# TelemetryModule.net
KiCad netlist of a schematic drawn in EAGLE
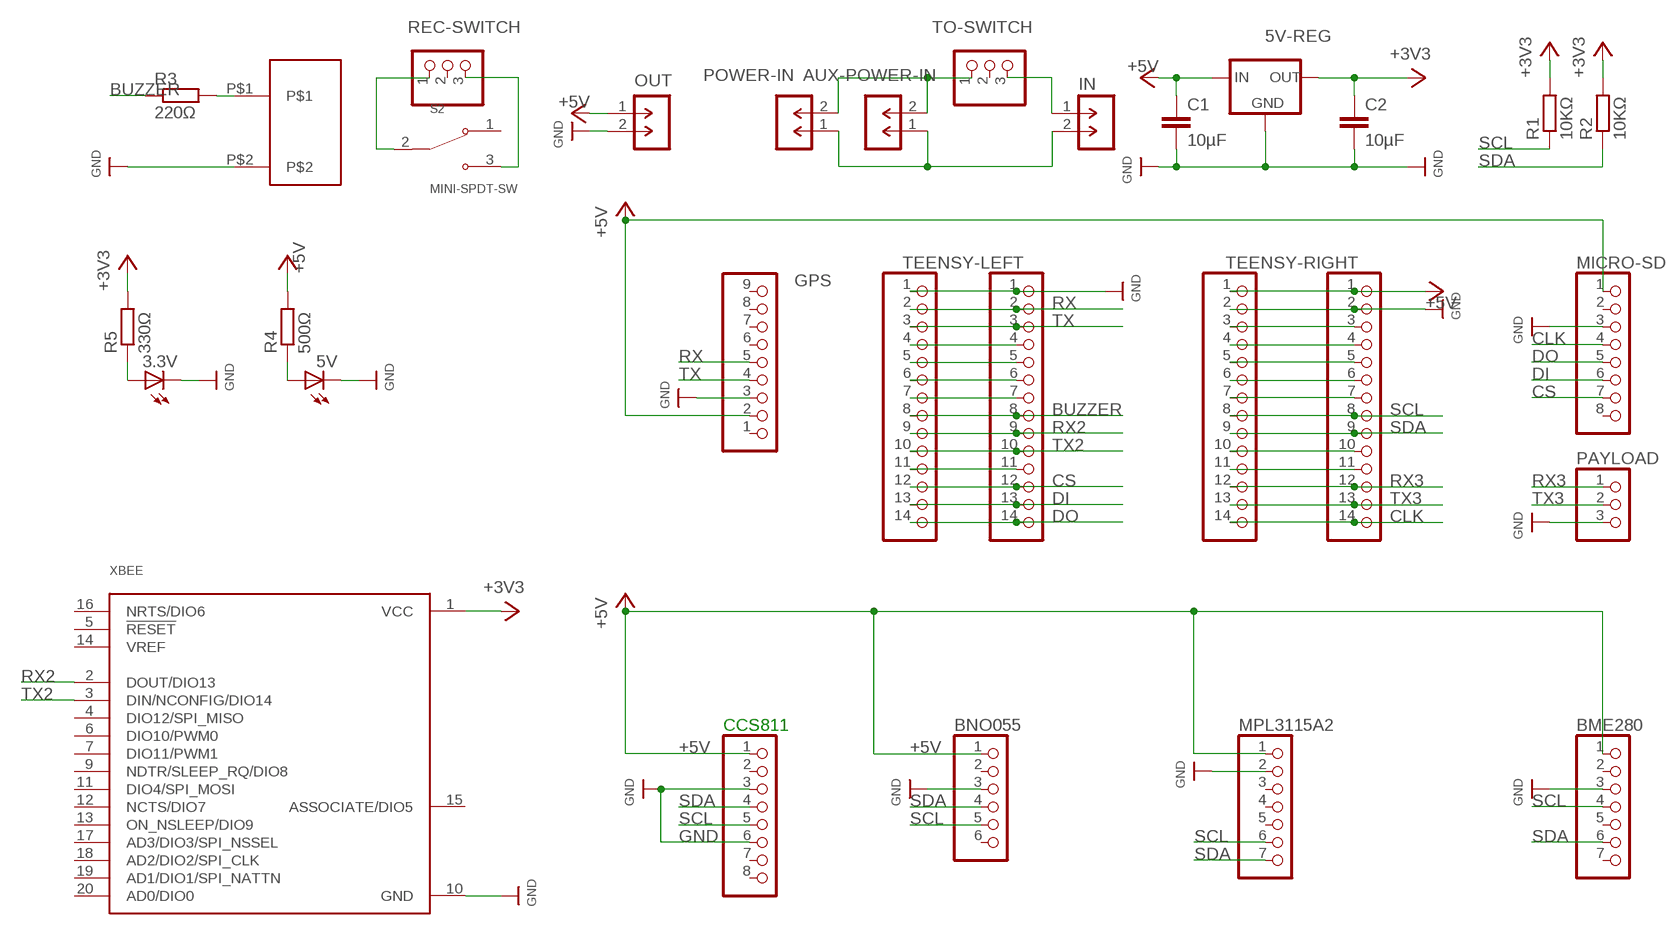
[diagram p0: schematic, sheet 1]

(export (version "E")
  (design (tool "Eeschema 10.0.6"))
  (components
    (comp (ref "3.3V")
      (value "LED5MM")
      (footprint "eagle-import:LED5MM")
      (libsource (lib "eagle-import") (part "LED5MM"))
    )
    (comp (ref "5V")
      (value "LED5MM")
      (footprint "eagle-import:LED5MM")
      (libsource (lib "eagle-import") (part "LED5MM"))
    )
    (comp (ref "5V-REG")
      (value "LD1117V33")
      (footprint "eagle-import:LD1117V33")
      (libsource (lib "eagle-import") (part "LD1117V33"))
    )
    (comp (ref "AUX-POWER-IN")
      (value "M-1X02-SIP-100-40Y")
      (footprint "eagle-import:SIP-100-02-40Y")
      (libsource (lib "eagle-import") (part "M-1X02-SIP-100-40Y"))
    )
    (comp (ref "BME280")
      (value "HEADER-1X770MIL")
      (footprint "eagle-import:1X07_ROUND_70")
      (libsource (lib "eagle-import") (part "HEADER-1X770MIL"))
    )
    (comp (ref "BNO055")
      (value "HEADER-1X676MIL")
      (footprint "eagle-import:1X06_ROUND_76")
      (libsource (lib "eagle-import") (part "HEADER-1X676MIL"))
    )
    (comp (ref "C1")
      (value "10µF")
      (footprint "eagle-import:C2.5-3")
      (libsource (lib "eagle-import") (part "C2,5-3"))
    )
    (comp (ref "C2")
      (value "10µF")
      (footprint "eagle-import:C2.5-3")
      (libsource (lib "eagle-import") (part "C2,5-3"))
    )
    (comp (ref "CCS811")
      (value "HEADER-1X870MIL")
      (footprint "eagle-import:1X08_ROUND_70")
      (libsource (lib "eagle-import") (part "HEADER-1X870MIL"))
    )
    (comp (ref "GPS")
      (value "HEADER-1X970MIL")
      (footprint "eagle-import:1X09_ROUND_70")
      (libsource (lib "eagle-import") (part "HEADER-1X970MIL"))
    )
    (comp (ref "IN")
      (value "M-1X02-SIP-100-40Y")
      (footprint "eagle-import:SIP-100-02-40Y")
      (libsource (lib "eagle-import") (part "M-1X02-SIP-100-40Y"))
    )
    (comp (ref "MICRO-SD")
      (value "PINHD-1X8BIG")
      (footprint "eagle-import:1X08-BIG")
      (libsource (lib "eagle-import") (part "PINHD-1X8BIG"))
    )
    (comp (ref "MPL3115A2")
      (value "HEADER-1X770MIL")
      (footprint "eagle-import:1X07_ROUND_70")
      (libsource (lib "eagle-import") (part "HEADER-1X770MIL"))
    )
    (comp (ref "OUT")
      (value "M-1X02-SIP-100-40Y")
      (footprint "eagle-import:SIP-100-02-40Y")
      (libsource (lib "eagle-import") (part "M-1X02-SIP-100-40Y"))
    )
    (comp (ref "PAYLOAD")
      (value "PINHD-1X3CB")
      (footprint "eagle-import:1X03-CLEANBIG")
      (libsource (lib "eagle-import") (part "PINHD-1X3CB"))
    )
    (comp (ref "POWER-IN")
      (value "M-1X02-SIP-100-40Y")
      (footprint "eagle-import:SIP-100-02-40Y")
      (libsource (lib "eagle-import") (part "M-1X02-SIP-100-40Y"))
    )
    (comp (ref "R1")
      (value "10KΩ")
      (footprint "eagle-import:0207_10")
      (libsource (lib "eagle-import") (part "R-EU_0207/10"))
    )
    (comp (ref "R2")
      (value "10KΩ")
      (footprint "eagle-import:0207_10")
      (libsource (lib "eagle-import") (part "R-EU_0207/10"))
    )
    (comp (ref "R3")
      (value "220Ω")
      (footprint "eagle-import:0207_10")
      (libsource (lib "eagle-import") (part "R-EU_0207/10"))
    )
    (comp (ref "R4")
      (value "500Ω")
      (footprint "eagle-import:0207_10")
      (libsource (lib "eagle-import") (part "R-EU_0207/10"))
    )
    (comp (ref "R5")
      (value "330Ω")
      (footprint "eagle-import:0207_10")
      (libsource (lib "eagle-import") (part "R-EU_0207/10"))
    )
    (comp (ref "REC-SWITCH")
      (value "PINHD-1X3CB")
      (footprint "eagle-import:1X03-CLEANBIG")
      (libsource (lib "eagle-import") (part "PINHD-1X3CB"))
    )
    (comp (ref "S2")
      (value "MINI-SPDT-SW")
      (footprint "eagle-import:SW_MINI-SPDT-SW")
      (fields (field (name "MF") "Gravitech"))
      (libsource (lib "eagle-import") (part "MINI-SPDT-SW"))
    )
    (comp (ref "TEENSY-LEFT")
      (value "PINHD-1X14-CB")
      (footprint "eagle-import:1X14-CB")
      (libsource (lib "eagle-import") (part "PINHD-1X14-CB"))
    )
    (comp (ref "TEENSY-LEFT-DUPE")
      (value "PINHD-1X14-CB")
      (footprint "eagle-import:1X14-CB")
      (libsource (lib "eagle-import") (part "PINHD-1X14-CB"))
    )
    (comp (ref "TEENSY-RIGHT")
      (value "PINHD-1X14-CB")
      (footprint "eagle-import:1X14-CB")
      (libsource (lib "eagle-import") (part "PINHD-1X14-CB"))
    )
    (comp (ref "TEENSY-RIGHT-DUPE")
      (value "PINHD-1X14-CB")
      (footprint "eagle-import:1X14-CB")
      (libsource (lib "eagle-import") (part "PINHD-1X14-CB"))
    )
    (comp (ref "TO-SWITCH")
      (value "PINHD-1X3CB")
      (footprint "eagle-import:1X03-CLEANBIG")
      (libsource (lib "eagle-import") (part "PINHD-1X3CB"))
    )
    (comp (ref "U$3")
      (value "PS1240P02BT")
      (footprint "eagle-import:PS1240P02BT")
      (fields (field (name "MF") "TDK"))
      (libsource (lib "eagle-import") (part "PS1240P02BT"))
    )
    (comp (ref "XBEE")
      (value "XBP9B-XCST-002")
      (footprint "eagle-import:DIP2200W51P200L3294H279Q20P")
      (fields (field (name "DIGI-KEY_PART_NUMBER") "602-1294-ND") (field (name "MF") "Digi International"))
      (libsource (lib "eagle-import") (part "XBP9B-XCST-002"))
    )
  )
  (nets
    (net (code "1") (name "+3V3") (class "Default")
      (node (ref "5V-REG") (pin "OUT") (pinfunction "OUT_OUT") (pintype "output"))
      (node (ref "C2") (pin "1") (pinfunction "1_1") (pintype "passive"))
      (node (ref "R1") (pin "2") (pinfunction "2_2") (pintype "passive"))
      (node (ref "R2") (pin "2") (pinfunction "2_2") (pintype "passive"))
      (node (ref "R5") (pin "2") (pinfunction "2_2") (pintype "passive"))
      (node (ref "XBEE") (pin "1") (pinfunction "VCC_1") (pintype "power_in"))
    )
    (net (code "2") (name "+5V") (class "Default")
      (node (ref "5V-REG") (pin "IN") (pinfunction "IN_IN") (pintype "input"))
      (node (ref "BME280") (pin "1") (pinfunction "1_1") (pintype "passive"))
      (node (ref "BNO055") (pin "1") (pinfunction "1_1") (pintype "passive"))
      (node (ref "C1") (pin "1") (pinfunction "1_1") (pintype "passive"))
      (node (ref "CCS811") (pin "1") (pinfunction "1_1") (pintype "passive"))
      (node (ref "GPS") (pin "2") (pinfunction "2_2") (pintype "passive"))
      (node (ref "MICRO-SD") (pin "1") (pinfunction "1_1") (pintype "passive"))
      (node (ref "MPL3115A2") (pin "1") (pinfunction "1_1") (pintype "passive"))
      (node (ref "OUT") (pin "1") (pinfunction "1_1") (pintype "passive"))
      (node (ref "R4") (pin "2") (pinfunction "2_2") (pintype "passive"))
      (node (ref "TEENSY-RIGHT") (pin "1") (pinfunction "1_1") (pintype "passive"))
      (node (ref "TEENSY-RIGHT-DUPE") (pin "1") (pinfunction "1_1") (pintype "passive"))
    )
    (net (code "3") (name "/BUZZER") (class "Default")
      (node (ref "R3") (pin "1") (pinfunction "1_1") (pintype "passive"))
      (node (ref "TEENSY-LEFT") (pin "8") (pinfunction "8_8") (pintype "passive"))
      (node (ref "TEENSY-LEFT-DUPE") (pin "8") (pinfunction "8_8") (pintype "passive"))
    )
    (net (code "4") (name "/CLK") (class "Default")
      (node (ref "MICRO-SD") (pin "4") (pinfunction "4_4") (pintype "passive"))
      (node (ref "TEENSY-RIGHT") (pin "14") (pinfunction "14_14") (pintype "passive"))
      (node (ref "TEENSY-RIGHT-DUPE") (pin "14") (pinfunction "14_14") (pintype "passive"))
    )
    (net (code "5") (name "/CS") (class "Default")
      (node (ref "MICRO-SD") (pin "7") (pinfunction "7_7") (pintype "passive"))
      (node (ref "TEENSY-LEFT") (pin "12") (pinfunction "12_12") (pintype "passive"))
      (node (ref "TEENSY-LEFT-DUPE") (pin "12") (pinfunction "12_12") (pintype "passive"))
    )
    (net (code "6") (name "/DI") (class "Default")
      (node (ref "MICRO-SD") (pin "6") (pinfunction "6_6") (pintype "passive"))
      (node (ref "TEENSY-LEFT") (pin "13") (pinfunction "13_13") (pintype "passive"))
      (node (ref "TEENSY-LEFT-DUPE") (pin "13") (pinfunction "13_13") (pintype "passive"))
    )
    (net (code "7") (name "/DO") (class "Default")
      (node (ref "MICRO-SD") (pin "5") (pinfunction "5_5") (pintype "passive"))
      (node (ref "TEENSY-LEFT") (pin "14") (pinfunction "14_14") (pintype "passive"))
      (node (ref "TEENSY-LEFT-DUPE") (pin "14") (pinfunction "14_14") (pintype "passive"))
    )
    (net (code "8") (name "/RX") (class "Default")
      (node (ref "GPS") (pin "5") (pinfunction "5_5") (pintype "passive"))
      (node (ref "TEENSY-LEFT") (pin "2") (pinfunction "2_2") (pintype "passive"))
      (node (ref "TEENSY-LEFT-DUPE") (pin "2") (pinfunction "2_2") (pintype "passive"))
    )
    (net (code "9") (name "/RX2") (class "Default")
      (node (ref "TEENSY-LEFT") (pin "9") (pinfunction "9_9") (pintype "passive"))
      (node (ref "TEENSY-LEFT-DUPE") (pin "9") (pinfunction "9_9") (pintype "passive"))
      (node (ref "XBEE") (pin "2") (pinfunction "DOUT/DIO13_2") (pintype "bidirectional"))
    )
    (net (code "10") (name "/RX3") (class "Default")
      (node (ref "PAYLOAD") (pin "1") (pinfunction "1_1") (pintype "passive"))
      (node (ref "TEENSY-RIGHT") (pin "12") (pinfunction "12_12") (pintype "passive"))
      (node (ref "TEENSY-RIGHT-DUPE") (pin "12") (pinfunction "12_12") (pintype "passive"))
    )
    (net (code "11") (name "/SCL") (class "Default")
      (node (ref "BME280") (pin "4") (pinfunction "4_4") (pintype "passive"))
      (node (ref "BNO055") (pin "5") (pinfunction "5_5") (pintype "passive"))
      (node (ref "CCS811") (pin "5") (pinfunction "5_5") (pintype "passive"))
      (node (ref "MPL3115A2") (pin "6") (pinfunction "6_6") (pintype "passive"))
      (node (ref "R1") (pin "1") (pinfunction "1_1") (pintype "passive"))
      (node (ref "TEENSY-RIGHT") (pin "8") (pinfunction "8_8") (pintype "passive"))
      (node (ref "TEENSY-RIGHT-DUPE") (pin "8") (pinfunction "8_8") (pintype "passive"))
    )
    (net (code "12") (name "/SDA") (class "Default")
      (node (ref "BME280") (pin "6") (pinfunction "6_6") (pintype "passive"))
      (node (ref "BNO055") (pin "4") (pinfunction "4_4") (pintype "passive"))
      (node (ref "CCS811") (pin "4") (pinfunction "4_4") (pintype "passive"))
      (node (ref "MPL3115A2") (pin "7") (pinfunction "7_7") (pintype "passive"))
      (node (ref "R2") (pin "1") (pinfunction "1_1") (pintype "passive"))
      (node (ref "TEENSY-RIGHT") (pin "9") (pinfunction "9_9") (pintype "passive"))
      (node (ref "TEENSY-RIGHT-DUPE") (pin "9") (pinfunction "9_9") (pintype "passive"))
    )
    (net (code "13") (name "/TX") (class "Default")
      (node (ref "GPS") (pin "4") (pinfunction "4_4") (pintype "passive"))
      (node (ref "TEENSY-LEFT") (pin "3") (pinfunction "3_3") (pintype "passive"))
      (node (ref "TEENSY-LEFT-DUPE") (pin "3") (pinfunction "3_3") (pintype "passive"))
    )
    (net (code "14") (name "/TX2") (class "Default")
      (node (ref "TEENSY-LEFT") (pin "10") (pinfunction "10_10") (pintype "passive"))
      (node (ref "TEENSY-LEFT-DUPE") (pin "10") (pinfunction "10_10") (pintype "passive"))
      (node (ref "XBEE") (pin "3") (pinfunction "DIN/NCONFIG/DIO14_3") (pintype "bidirectional"))
    )
    (net (code "15") (name "/TX3") (class "Default")
      (node (ref "PAYLOAD") (pin "2") (pinfunction "2_2") (pintype "passive"))
      (node (ref "TEENSY-RIGHT") (pin "13") (pinfunction "13_13") (pintype "passive"))
      (node (ref "TEENSY-RIGHT-DUPE") (pin "13") (pinfunction "13_13") (pintype "passive"))
    )
    (net (code "16") (name "GND") (class "Default")
      (node (ref "3.3V") (pin "K") (pinfunction "C_K") (pintype "passive"))
      (node (ref "5V") (pin "K") (pinfunction "C_K") (pintype "passive"))
      (node (ref "5V-REG") (pin "GND") (pinfunction "GND_GND") (pintype "input"))
      (node (ref "BME280") (pin "3") (pinfunction "3_3") (pintype "passive"))
      (node (ref "BNO055") (pin "3") (pinfunction "3_3") (pintype "passive"))
      (node (ref "C1") (pin "2") (pinfunction "2_2") (pintype "passive"))
      (node (ref "C2") (pin "2") (pinfunction "2_2") (pintype "passive"))
      (node (ref "CCS811") (pin "3") (pinfunction "3_3") (pintype "passive"))
      (node (ref "CCS811") (pin "6") (pinfunction "6_6") (pintype "passive"))
      (node (ref "GPS") (pin "3") (pinfunction "3_3") (pintype "passive"))
      (node (ref "MICRO-SD") (pin "3") (pinfunction "3_3") (pintype "passive"))
      (node (ref "MPL3115A2") (pin "2") (pinfunction "2_2") (pintype "passive"))
      (node (ref "OUT") (pin "2") (pinfunction "2_2") (pintype "passive"))
      (node (ref "PAYLOAD") (pin "3") (pinfunction "3_3") (pintype "passive"))
      (node (ref "TEENSY-LEFT") (pin "1") (pinfunction "1_1") (pintype "passive"))
      (node (ref "TEENSY-LEFT-DUPE") (pin "1") (pinfunction "1_1") (pintype "passive"))
      (node (ref "TEENSY-RIGHT") (pin "2") (pinfunction "2_2") (pintype "passive"))
      (node (ref "TEENSY-RIGHT-DUPE") (pin "2") (pinfunction "2_2") (pintype "passive"))
      (node (ref "U$3") (pin "P$2") (pinfunction "P$2_P$2") (pintype "bidirectional"))
      (node (ref "XBEE") (pin "10") (pinfunction "GND_10") (pintype "power_in"))
    )
    (net (code "17") (name "Net-(3.3V-PadA)") (class "Default")
      (node (ref "3.3V") (pin "A") (pinfunction "A_A") (pintype "passive"))
      (node (ref "R5") (pin "1") (pinfunction "1_1") (pintype "passive"))
    )
    (net (code "18") (name "Net-(5V-PadA)") (class "Default")
      (node (ref "5V") (pin "A") (pinfunction "A_A") (pintype "passive"))
      (node (ref "R4") (pin "1") (pinfunction "1_1") (pintype "passive"))
    )
    (net (code "19") (name "Net-(AUX-POWER-IN-Pad1)") (class "Default")
      (node (ref "AUX-POWER-IN") (pin "1") (pinfunction "1_1") (pintype "passive"))
      (node (ref "IN") (pin "2") (pinfunction "2_2") (pintype "passive"))
      (node (ref "POWER-IN") (pin "1") (pinfunction "1_1") (pintype "passive"))
    )
    (net (code "20") (name "Net-(AUX-POWER-IN-Pad2)") (class "Default")
      (node (ref "AUX-POWER-IN") (pin "2") (pinfunction "2_2") (pintype "passive"))
      (node (ref "POWER-IN") (pin "2") (pinfunction "2_2") (pintype "passive"))
      (node (ref "TO-SWITCH") (pin "1") (pinfunction "1_1") (pintype "passive"))
    )
    (net (code "21") (name "Net-(IN-Pad1)") (class "Default")
      (node (ref "IN") (pin "1") (pinfunction "1_1") (pintype "passive"))
      (node (ref "TO-SWITCH") (pin "3") (pinfunction "3_3") (pintype "passive"))
    )
    (net (code "22") (name "Net-(R3-Pad2)") (class "Default")
      (node (ref "R3") (pin "2") (pinfunction "2_2") (pintype "passive"))
      (node (ref "U$3") (pin "P$1") (pinfunction "P$1_P$1") (pintype "bidirectional"))
    )
    (net (code "23") (name "Net-(REC-SWITCH-Pad1)") (class "Default")
      (node (ref "REC-SWITCH") (pin "1") (pinfunction "1_1") (pintype "passive"))
      (node (ref "S2") (pin "2") (pinfunction "2_2") (pintype "passive"))
    )
    (net (code "24") (name "Net-(REC-SWITCH-Pad3)") (class "Default")
      (node (ref "REC-SWITCH") (pin "3") (pinfunction "3_3") (pintype "passive"))
      (node (ref "S2") (pin "3") (pinfunction "3_3") (pintype "passive"))
    )
    (net (code "25") (name "Net-(TEENSY-LEFT-DUPE-Pad4)") (class "Default")
      (node (ref "TEENSY-LEFT") (pin "4") (pinfunction "4_4") (pintype "passive"))
      (node (ref "TEENSY-LEFT-DUPE") (pin "4") (pinfunction "4_4") (pintype "passive"))
    )
    (net (code "26") (name "Net-(TEENSY-LEFT-DUPE-Pad5)") (class "Default")
      (node (ref "TEENSY-LEFT") (pin "5") (pinfunction "5_5") (pintype "passive"))
      (node (ref "TEENSY-LEFT-DUPE") (pin "5") (pinfunction "5_5") (pintype "passive"))
    )
    (net (code "27") (name "Net-(TEENSY-LEFT-DUPE-Pad6)") (class "Default")
      (node (ref "TEENSY-LEFT") (pin "6") (pinfunction "6_6") (pintype "passive"))
      (node (ref "TEENSY-LEFT-DUPE") (pin "6") (pinfunction "6_6") (pintype "passive"))
    )
    (net (code "28") (name "Net-(TEENSY-LEFT-DUPE-Pad7)") (class "Default")
      (node (ref "TEENSY-LEFT") (pin "7") (pinfunction "7_7") (pintype "passive"))
      (node (ref "TEENSY-LEFT-DUPE") (pin "7") (pinfunction "7_7") (pintype "passive"))
    )
    (net (code "29") (name "Net-(TEENSY-LEFT-DUPE-Pad11)") (class "Default")
      (node (ref "TEENSY-LEFT") (pin "11") (pinfunction "11_11") (pintype "passive"))
      (node (ref "TEENSY-LEFT-DUPE") (pin "11") (pinfunction "11_11") (pintype "passive"))
    )
    (net (code "30") (name "Net-(TEENSY-RIGHT-DUPE-Pad3)") (class "Default")
      (node (ref "TEENSY-RIGHT") (pin "3") (pinfunction "3_3") (pintype "passive"))
      (node (ref "TEENSY-RIGHT-DUPE") (pin "3") (pinfunction "3_3") (pintype "passive"))
    )
    (net (code "31") (name "Net-(TEENSY-RIGHT-DUPE-Pad4)") (class "Default")
      (node (ref "TEENSY-RIGHT") (pin "4") (pinfunction "4_4") (pintype "passive"))
      (node (ref "TEENSY-RIGHT-DUPE") (pin "4") (pinfunction "4_4") (pintype "passive"))
    )
    (net (code "32") (name "Net-(TEENSY-RIGHT-DUPE-Pad5)") (class "Default")
      (node (ref "TEENSY-RIGHT") (pin "5") (pinfunction "5_5") (pintype "passive"))
      (node (ref "TEENSY-RIGHT-DUPE") (pin "5") (pinfunction "5_5") (pintype "passive"))
    )
    (net (code "33") (name "Net-(TEENSY-RIGHT-DUPE-Pad6)") (class "Default")
      (node (ref "TEENSY-RIGHT") (pin "6") (pinfunction "6_6") (pintype "passive"))
      (node (ref "TEENSY-RIGHT-DUPE") (pin "6") (pinfunction "6_6") (pintype "passive"))
    )
    (net (code "34") (name "Net-(TEENSY-RIGHT-DUPE-Pad7)") (class "Default")
      (node (ref "TEENSY-RIGHT") (pin "7") (pinfunction "7_7") (pintype "passive"))
      (node (ref "TEENSY-RIGHT-DUPE") (pin "7") (pinfunction "7_7") (pintype "passive"))
    )
    (net (code "35") (name "Net-(TEENSY-RIGHT-DUPE-Pad10)") (class "Default")
      (node (ref "TEENSY-RIGHT") (pin "10") (pinfunction "10_10") (pintype "passive"))
      (node (ref "TEENSY-RIGHT-DUPE") (pin "10") (pinfunction "10_10") (pintype "passive"))
    )
    (net (code "36") (name "Net-(TEENSY-RIGHT-DUPE-Pad11)") (class "Default")
      (node (ref "TEENSY-RIGHT") (pin "11") (pinfunction "11_11") (pintype "passive"))
      (node (ref "TEENSY-RIGHT-DUPE") (pin "11") (pinfunction "11_11") (pintype "passive"))
    )
    (net (code "37") (name "unconnected-(BME280-Pad2)") (class "Default")
      (node (ref "BME280") (pin "2") (pinfunction "2_2") (pintype "passive"))
    )
    (net (code "38") (name "unconnected-(BME280-Pad5)") (class "Default")
      (node (ref "BME280") (pin "5") (pinfunction "5_5") (pintype "passive"))
    )
    (net (code "39") (name "unconnected-(BME280-Pad7)") (class "Default")
      (node (ref "BME280") (pin "7") (pinfunction "7_7") (pintype "passive"))
    )
    (net (code "40") (name "unconnected-(BNO055-Pad2)") (class "Default")
      (node (ref "BNO055") (pin "2") (pinfunction "2_2") (pintype "passive"))
    )
    (net (code "41") (name "unconnected-(BNO055-Pad6)") (class "Default")
      (node (ref "BNO055") (pin "6") (pinfunction "6_6") (pintype "passive"))
    )
    (net (code "42") (name "unconnected-(CCS811-Pad2)") (class "Default")
      (node (ref "CCS811") (pin "2") (pinfunction "2_2") (pintype "passive"))
    )
    (net (code "43") (name "unconnected-(CCS811-Pad7)") (class "Default")
      (node (ref "CCS811") (pin "7") (pinfunction "7_7") (pintype "passive"))
    )
    (net (code "44") (name "unconnected-(CCS811-Pad8)") (class "Default")
      (node (ref "CCS811") (pin "8") (pinfunction "8_8") (pintype "passive"))
    )
    (net (code "45") (name "unconnected-(GPS-Pad1)") (class "Default")
      (node (ref "GPS") (pin "1") (pinfunction "1_1") (pintype "passive"))
    )
    (net (code "46") (name "unconnected-(GPS-Pad6)") (class "Default")
      (node (ref "GPS") (pin "6") (pinfunction "6_6") (pintype "passive"))
    )
    (net (code "47") (name "unconnected-(GPS-Pad7)") (class "Default")
      (node (ref "GPS") (pin "7") (pinfunction "7_7") (pintype "passive"))
    )
    (net (code "48") (name "unconnected-(GPS-Pad8)") (class "Default")
      (node (ref "GPS") (pin "8") (pinfunction "8_8") (pintype "passive"))
    )
    (net (code "49") (name "unconnected-(GPS-Pad9)") (class "Default")
      (node (ref "GPS") (pin "9") (pinfunction "9_9") (pintype "passive"))
    )
    (net (code "50") (name "unconnected-(MICRO-SD-Pad2)") (class "Default")
      (node (ref "MICRO-SD") (pin "2") (pinfunction "2_2") (pintype "passive"))
    )
    (net (code "51") (name "unconnected-(MICRO-SD-Pad8)") (class "Default")
      (node (ref "MICRO-SD") (pin "8") (pinfunction "8_8") (pintype "passive"))
    )
    (net (code "52") (name "unconnected-(MPL3115A2-Pad3)") (class "Default")
      (node (ref "MPL3115A2") (pin "3") (pinfunction "3_3") (pintype "passive"))
    )
    (net (code "53") (name "unconnected-(MPL3115A2-Pad4)") (class "Default")
      (node (ref "MPL3115A2") (pin "4") (pinfunction "4_4") (pintype "passive"))
    )
    (net (code "54") (name "unconnected-(MPL3115A2-Pad5)") (class "Default")
      (node (ref "MPL3115A2") (pin "5") (pinfunction "5_5") (pintype "passive"))
    )
    (net (code "55") (name "unconnected-(REC-SWITCH-Pad2)") (class "Default")
      (node (ref "REC-SWITCH") (pin "2") (pinfunction "2_2") (pintype "passive"))
    )
    (net (code "56") (name "unconnected-(S2-Pad1)") (class "Default")
      (node (ref "S2") (pin "1") (pinfunction "1_1") (pintype "passive"))
    )
    (net (code "57") (name "unconnected-(TO-SWITCH-Pad2)") (class "Default")
      (node (ref "TO-SWITCH") (pin "2") (pinfunction "2_2") (pintype "passive"))
    )
    (net (code "58") (name "unconnected-(XBEE-AD0{slash}DIO0-Pad20)") (class "Default")
      (node (ref "XBEE") (pin "20") (pinfunction "AD0/DIO0_20") (pintype "bidirectional"))
    )
    (net (code "59") (name "unconnected-(XBEE-AD1{slash}DIO1{slash}SPI_NATTN-Pad19)") (class "Default")
      (node (ref "XBEE") (pin "19") (pinfunction "AD1/DIO1/SPI_NATTN_19") (pintype "bidirectional"))
    )
    (net (code "60") (name "unconnected-(XBEE-AD2{slash}DIO2{slash}SPI_CLK-Pad18)") (class "Default")
      (node (ref "XBEE") (pin "18") (pinfunction "AD2/DIO2/SPI_CLK_18") (pintype "bidirectional"))
    )
    (net (code "61") (name "unconnected-(XBEE-AD3{slash}DIO3{slash}SPI_NSSEL-Pad17)") (class "Default")
      (node (ref "XBEE") (pin "17") (pinfunction "AD3/DIO3/SPI_NSSEL_17") (pintype "bidirectional"))
    )
    (net (code "62") (name "unconnected-(XBEE-ASSOCIATE{slash}DIO5-Pad15)") (class "Default")
      (node (ref "XBEE") (pin "15") (pinfunction "ASSOCIATE/DIO5_15") (pintype "output"))
    )
    (net (code "63") (name "unconnected-(XBEE-DIO4{slash}SPI_MOSI-Pad11)") (class "Default")
      (node (ref "XBEE") (pin "11") (pinfunction "DIO4/SPI_MOSI_11") (pintype "bidirectional"))
    )
    (net (code "64") (name "unconnected-(XBEE-DIO10{slash}PWM0-Pad6)") (class "Default")
      (node (ref "XBEE") (pin "6") (pinfunction "DIO10/PWM0_6") (pintype "bidirectional"))
    )
    (net (code "65") (name "unconnected-(XBEE-DIO11{slash}PWM1-Pad7)") (class "Default")
      (node (ref "XBEE") (pin "7") (pinfunction "DIO11/PWM1_7") (pintype "bidirectional"))
    )
    (net (code "66") (name "unconnected-(XBEE-DIO12{slash}SPI_MISO-Pad4)") (class "Default")
      (node (ref "XBEE") (pin "4") (pinfunction "DIO12/SPI_MISO_4") (pintype "bidirectional"))
    )
    (net (code "67") (name "unconnected-(XBEE-NCTS{slash}DIO7-Pad12)") (class "Default")
      (node (ref "XBEE") (pin "12") (pinfunction "NCTS/DIO7_12") (pintype "bidirectional"))
    )
    (net (code "68") (name "unconnected-(XBEE-NDTR{slash}SLEEP_RQ{slash}DIO8-Pad9)") (class "Default")
      (node (ref "XBEE") (pin "9") (pinfunction "NDTR/SLEEP_RQ/DIO8_9") (pintype "bidirectional"))
    )
    (net (code "69") (name "unconnected-(XBEE-NRTS{slash}DIO6-Pad16)") (class "Default")
      (node (ref "XBEE") (pin "16") (pinfunction "NRTS/DIO6_16") (pintype "input"))
    )
    (net (code "70") (name "unconnected-(XBEE-ON_NSLEEP{slash}DIO9-Pad13)") (class "Default")
      (node (ref "XBEE") (pin "13") (pinfunction "ON_NSLEEP/DIO9_13") (pintype "bidirectional"))
    )
    (net (code "71") (name "unconnected-(XBEE-VREF-Pad14)") (class "Default")
      (node (ref "XBEE") (pin "14") (pinfunction "VREF_14") (pintype "input"))
    )
    (net (code "72") (name "unconnected-(XBEE-~{RESET}-Pad5)") (class "Default")
      (node (ref "XBEE") (pin "5") (pinfunction "~{RESET}_5") (pintype "input"))
    )
  )
)
